# Power.net
KiCad netlist of a schematic drawn in Altium Designer
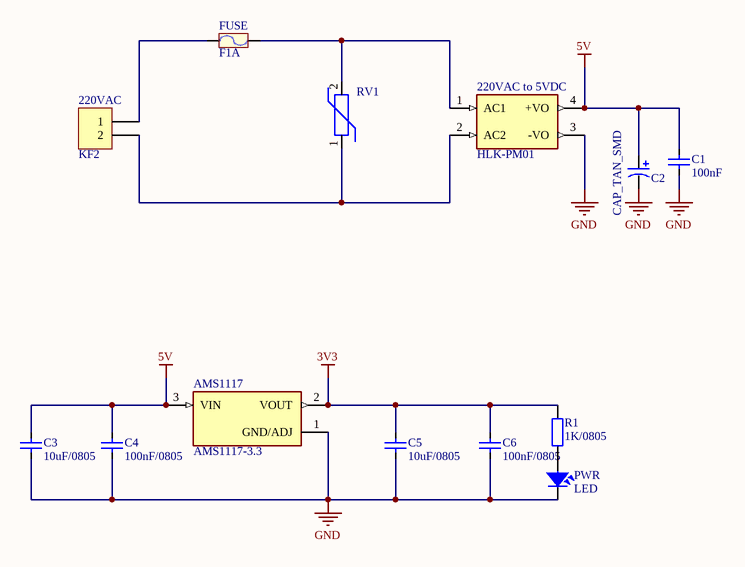
[diagram p0: Power.SchDoc]

(export (version "E")
  (design (tool "Eeschema 10.0.6"))
  (components
    (comp (ref "220VAC")
      (value "KF2")
      (footprint "KF2-7.62")
      (fields
        (field (name "MANUFACTURER") "Würth Elektronik eiSos GmbH")
        (field (name "PARTNO") "691103110002")
        (field (name "CREATED BY") "Karrer Zheng")
      )
      (libsource (lib "My Library") (part "KF2"))
    )
    (comp (ref "220VAC to 5VDC")
      (value "HLK-PM01")
      (footprint "CONV_HLK-PM01")
      (fields (field (name "MF") "Hi-link") (field (name "MP") "hlk-pm01"))
      (libsource (lib "HLK-PM01") (part "HLK-PM01"))
    )
    (comp (ref "AMS1117")
      (value "AMS1117-3.3")
      (footprint "SOT229P700X180-4N")
      (description "Sot223/Pkg 1-Amp 3.3-Volt Low Drop Out Voltage Regulatator")
      (fields (field (name "MF") "Advanced Monolithic Systems"))
      (libsource (lib "AMS1117-3.3") (part "AMS1117-3.3"))
    )
    (comp (ref "C1")
      (value "100nF")
      (footprint "CAP_0402")
      (description "Capacitor")
      (fields (field (name "PUBLISHER") "Altium Limited"))
      (libsource (lib "My Library") (part "CapSMD"))
    )
    (comp (ref "C2")
      (value "CAP_TAN_SMD")
      (footprint "CAP_7343")
      (description "Polazied Tantalum Capacitor")
      (libsource (lib "My Library") (part "CAP_TAN_SMD"))
    )
    (comp (ref "C3")
      (value "10uF/0805")
      (footprint "CAP_0805")
      (description "Capacitor")
      (fields (field (name "PUBLISHER") "Altium Limited"))
      (libsource (lib "My Library") (part "CapSMD"))
    )
    (comp (ref "C4")
      (value "100nF/0805")
      (footprint "CAP_0805")
      (description "Capacitor")
      (fields (field (name "PUBLISHER") "Altium Limited"))
      (libsource (lib "My Library") (part "CapSMD"))
    )
    (comp (ref "C5")
      (value "10uF/0805")
      (footprint "CAP_0805")
      (description "Capacitor")
      (fields (field (name "PUBLISHER") "Altium Limited"))
      (libsource (lib "My Library") (part "CapSMD"))
    )
    (comp (ref "C6")
      (value "100nF/0805")
      (footprint "CAP_0805")
      (description "Capacitor")
      (fields (field (name "PUBLISHER") "Altium Limited"))
      (libsource (lib "My Library") (part "CapSMD"))
    )
    (comp (ref "FUSE")
      (value "F1A")
      (footprint "Fuse4")
      (description "Fuse")
      (fields (field (name "DESIGNED BY") "VanDungEvn"))
      (libsource (lib "My Library") (part "Fuse"))
    )
    (comp (ref "PWR")
      (value "LED")
      (footprint "LED-0805-Green")
      (description "LED Single colour Green and Red")
      (libsource (lib "My Library") (part "LED"))
    )
    (comp (ref "R1")
      (value "1K/0805")
      (footprint "RES-SMD-0805")
      (description "Resistor SMD")
      (fields
        (field (name "MANUFACTURER") "Generic Components")
        (field (name "PUBLISHER") "Altium Hobart Technology Centre")
      )
      (libsource (lib "My Library") (part "Resistor - SMD"))
    )
    (comp (ref "RV1")
      (value "MOV-14D471K")
      (footprint "MOV14D471K")
      (description "470 V 4.5 kA Varistor 1 Circuit Through Hole Disc 14mm")
      (fields (field (name "MF") "Bourns"))
      (libsource (lib "MOV-14D471K-Tu-Chong-Set") (part "MOV-14D471K"))
    )
  )
  (nets
    (net (code "1") (name "3V3") (class "Default")
      (node (ref "AMS1117") (pin "2") (pinfunction "VOUT_2") (pintype "output"))
      (node (ref "C5") (pin "2") (pinfunction "2_2") (pintype "passive"))
      (node (ref "C6") (pin "2") (pinfunction "2_2") (pintype "passive"))
      (node (ref "R1") (pin "1") (pinfunction "1_1") (pintype "passive"))
    )
    (net (code "2") (name "5V") (class "Default")
      (node (ref "220VAC to 5VDC") (pin "4") (pinfunction "+VO_4") (pintype "output"))
      (node (ref "AMS1117") (pin "3") (pinfunction "VIN_3") (pintype "input"))
      (node (ref "C1") (pin "2") (pinfunction "2_2") (pintype "passive"))
      (node (ref "C2") (pin "1") (pinfunction "1_1") (pintype "passive"))
      (node (ref "C3") (pin "2") (pinfunction "2_2") (pintype "passive"))
      (node (ref "C4") (pin "2") (pinfunction "2_2") (pintype "passive"))
    )
    (net (code "3") (name "GND") (class "Default")
      (node (ref "220VAC to 5VDC") (pin "3") (pinfunction "-VO_3") (pintype "output"))
      (node (ref "AMS1117") (pin "1") (pinfunction "GND/ADJ_1") (pintype "power_in"))
      (node (ref "C1") (pin "1") (pinfunction "1_1") (pintype "passive"))
      (node (ref "C2") (pin "2") (pinfunction "2_2") (pintype "passive"))
      (node (ref "C3") (pin "1") (pinfunction "1_1") (pintype "passive"))
      (node (ref "C4") (pin "1") (pinfunction "1_1") (pintype "passive"))
      (node (ref "C5") (pin "1") (pinfunction "1_1") (pintype "passive"))
      (node (ref "C6") (pin "1") (pinfunction "1_1") (pintype "passive"))
      (node (ref "PWR") (pin "2") (pinfunction "2_2") (pintype "passive"))
    )
    (net (code "4") (name "Net-(220VAC to 5VDC-AC1)") (class "Default")
      (node (ref "220VAC to 5VDC") (pin "1") (pinfunction "AC1_1") (pintype "input"))
      (node (ref "FUSE") (pin "2") (pinfunction "2_2") (pintype "passive"))
      (node (ref "RV1") (pin "2") (pinfunction "2_2") (pintype "bidirectional"))
    )
    (net (code "5") (name "Net-(220VAC to 5VDC-AC2)") (class "Default")
      (node (ref "220VAC") (pin "2") (pinfunction "2_2") (pintype "passive"))
      (node (ref "220VAC to 5VDC") (pin "2") (pinfunction "AC2_2") (pintype "input"))
      (node (ref "RV1") (pin "1") (pinfunction "1_1") (pintype "bidirectional"))
    )
    (net (code "6") (name "Net-(220VAC-Pad1)") (class "Default")
      (node (ref "220VAC") (pin "1") (pinfunction "1_1") (pintype "passive"))
      (node (ref "FUSE") (pin "1") (pinfunction "1_1") (pintype "passive"))
    )
    (net (code "7") (name "Net-(PWR-Pad1)") (class "Default")
      (node (ref "PWR") (pin "1") (pinfunction "1_1") (pintype "passive"))
      (node (ref "R1") (pin "2") (pinfunction "2_2") (pintype "passive"))
    )
  )
)
